# envca_4hp_2v.net
KiCad netlist of a schematic drawn in EAGLE
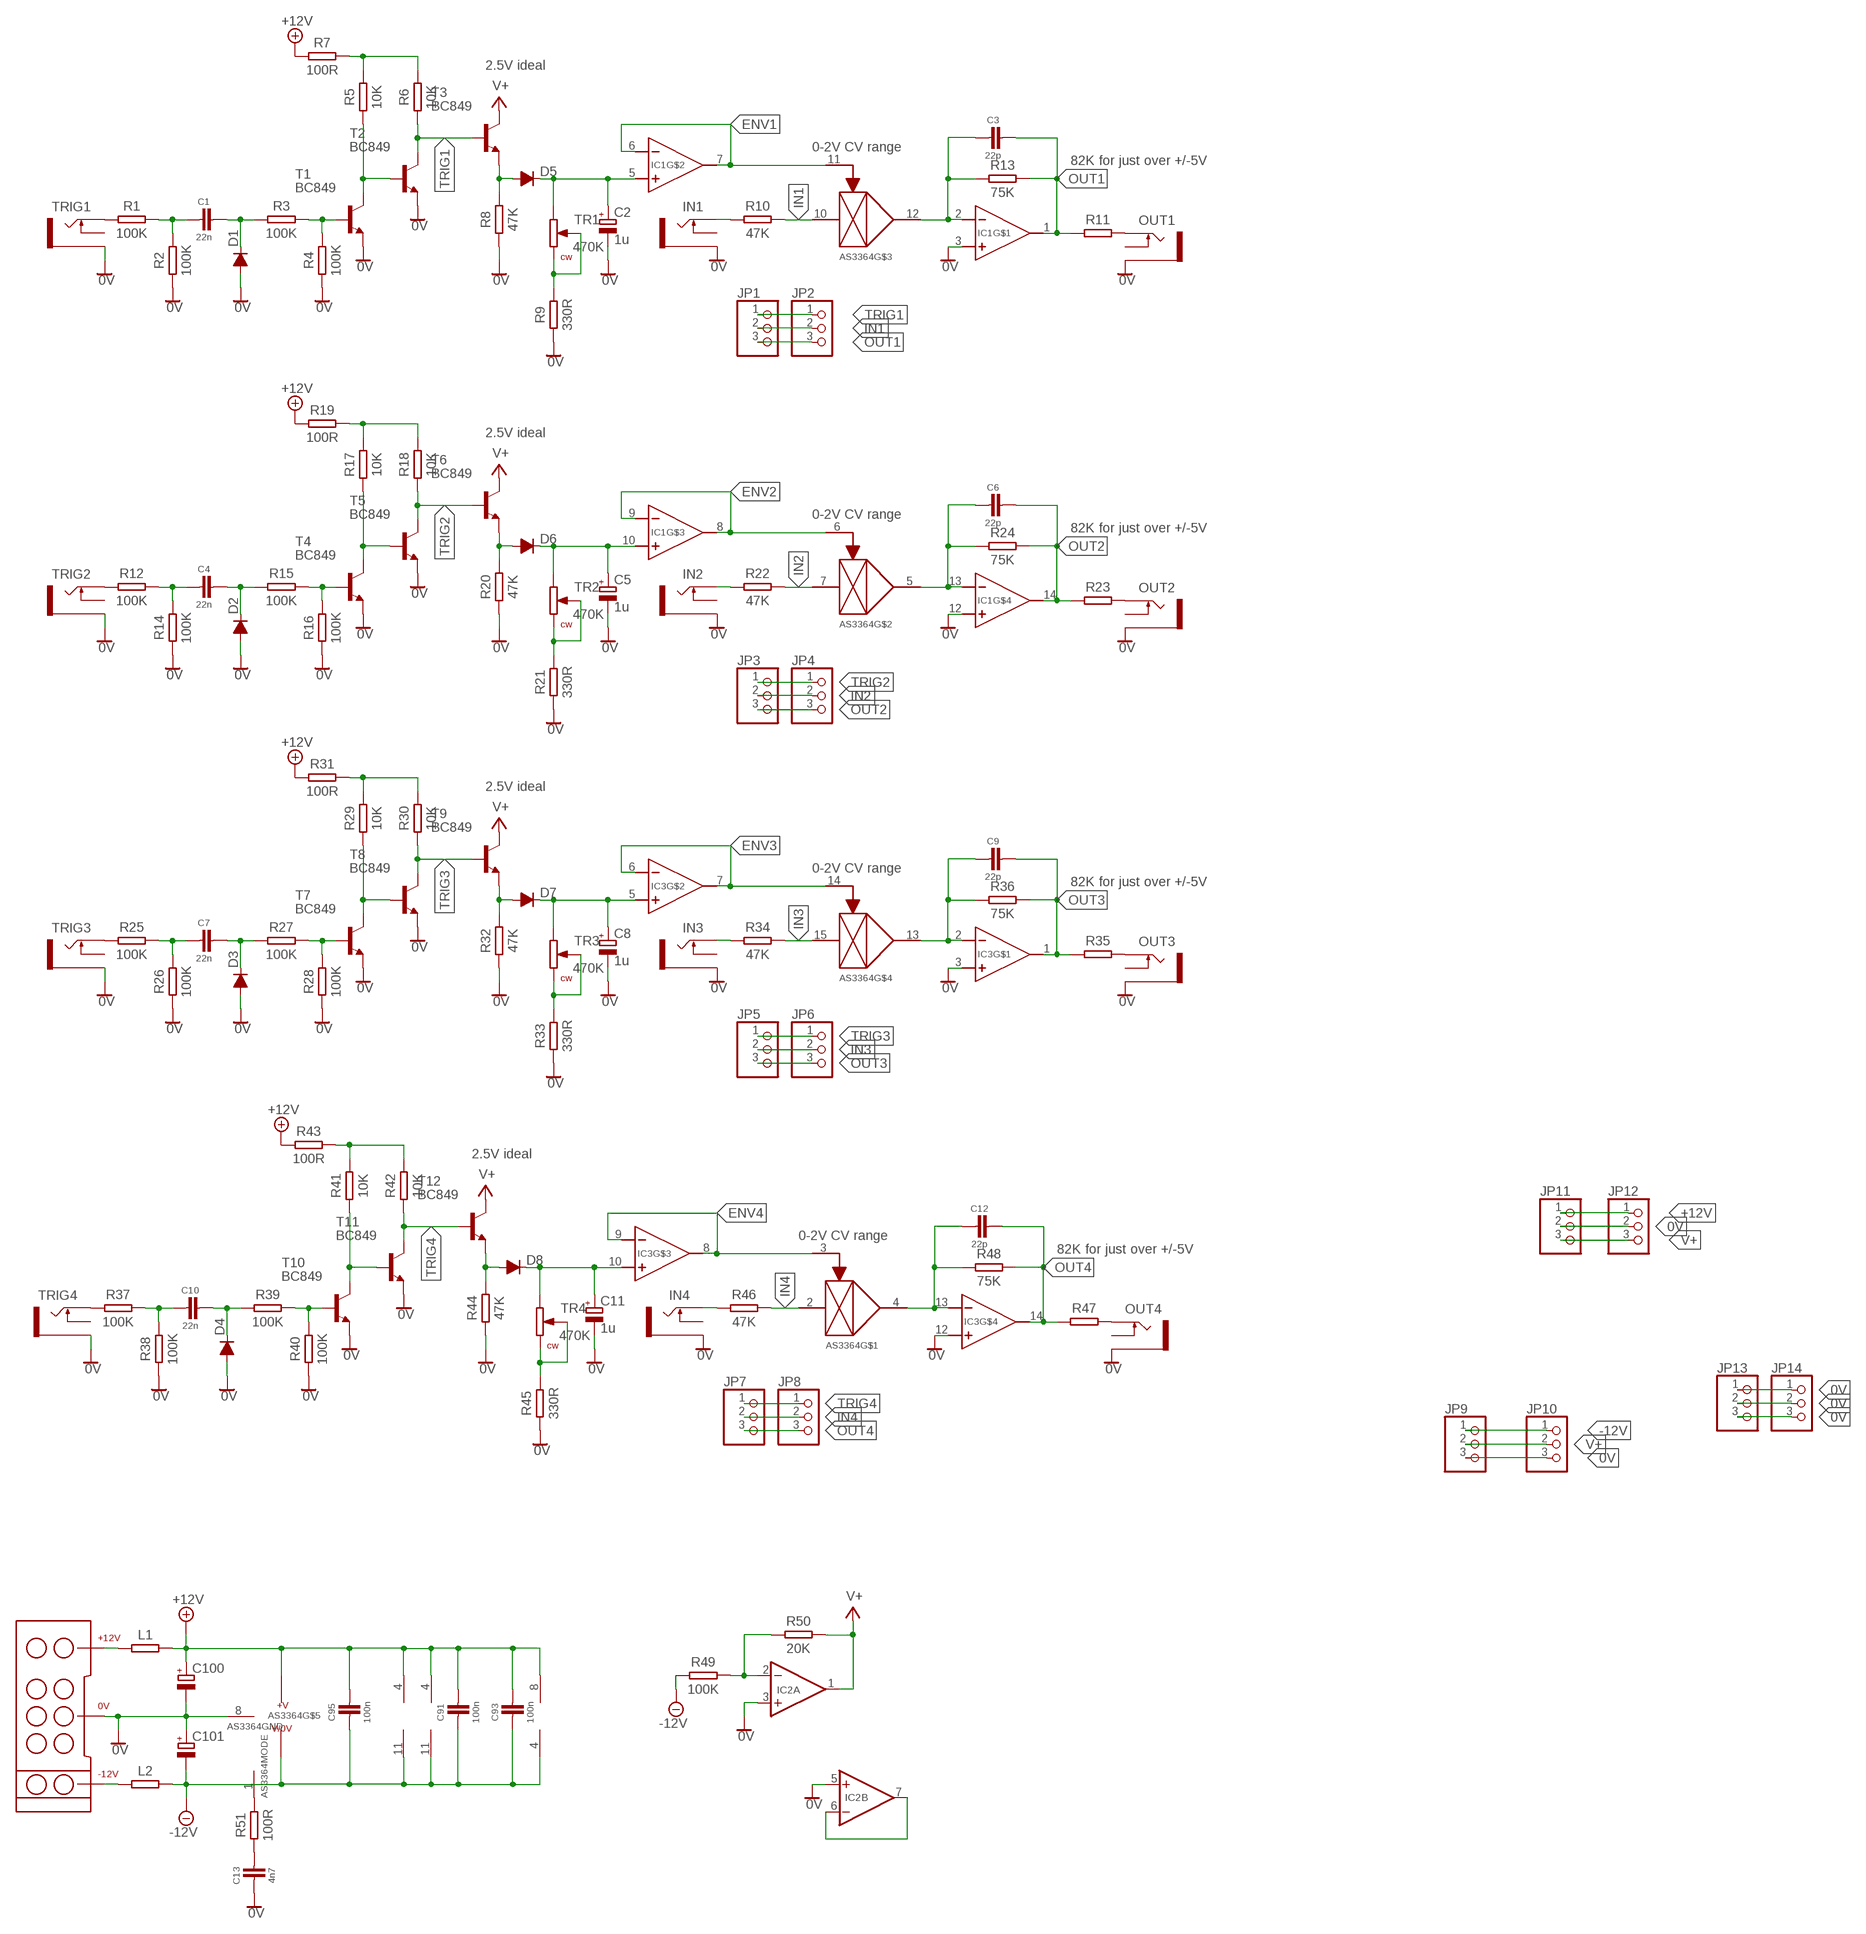
[diagram p0: schematic, sheet 1]

(export (version "E")
  (design (tool "Eeschema 10.0.6"))
  (components
    (comp (ref "AS3364")
      (value "AS2164_SMD")
      (footprint "eagle-import:SO16")
      (libsource (lib "eagle-import") (part "AS2164_SMD"))
    )
    (comp (ref "C1")
      (value "22n")
      (footprint "eagle-import:C0805")
      (libsource (lib "eagle-import") (part "CAP_0805"))
    )
    (comp (ref "C2")
      (value "1u")
      (footprint "eagle-import:E2,5-6")
      (libsource (lib "eagle-import") (part "CPOL-EUE2.5-6"))
    )
    (comp (ref "C3")
      (value "22p")
      (footprint "eagle-import:C0805")
      (libsource (lib "eagle-import") (part "CAP_0805"))
    )
    (comp (ref "C4")
      (value "22n")
      (footprint "eagle-import:C0805")
      (libsource (lib "eagle-import") (part "CAP_0805"))
    )
    (comp (ref "C5")
      (value "1u")
      (footprint "eagle-import:E2,5-6")
      (libsource (lib "eagle-import") (part "CPOL-EUE2.5-6"))
    )
    (comp (ref "C6")
      (value "22p")
      (footprint "eagle-import:C0805")
      (libsource (lib "eagle-import") (part "CAP_0805"))
    )
    (comp (ref "C7")
      (value "22n")
      (footprint "eagle-import:C0805")
      (libsource (lib "eagle-import") (part "CAP_0805"))
    )
    (comp (ref "C8")
      (value "1u")
      (footprint "eagle-import:E2,5-6")
      (libsource (lib "eagle-import") (part "CPOL-EUE2.5-6"))
    )
    (comp (ref "C9")
      (value "22p")
      (footprint "eagle-import:C0805")
      (libsource (lib "eagle-import") (part "CAP_0805"))
    )
    (comp (ref "C10")
      (value "22n")
      (footprint "eagle-import:C0805")
      (libsource (lib "eagle-import") (part "CAP_0805"))
    )
    (comp (ref "C11")
      (value "1u")
      (footprint "eagle-import:E2,5-6")
      (libsource (lib "eagle-import") (part "CPOL-EUE2.5-6"))
    )
    (comp (ref "C12")
      (value "22p")
      (footprint "eagle-import:C0805")
      (libsource (lib "eagle-import") (part "CAP_0805"))
    )
    (comp (ref "C13")
      (value "4n7")
      (footprint "eagle-import:C0805")
      (libsource (lib "eagle-import") (part "CAP_0805"))
    )
    (comp (ref "C91")
      (value "100n")
      (footprint "eagle-import:C0805")
      (libsource (lib "eagle-import") (part "CAP_0805"))
    )
    (comp (ref "C93")
      (value "100n")
      (footprint "eagle-import:C0805")
      (libsource (lib "eagle-import") (part "CAP_0805"))
    )
    (comp (ref "C95")
      (value "100n")
      (footprint "eagle-import:C0805")
      (libsource (lib "eagle-import") (part "CAP_0805"))
    )
    (comp (ref "C100")
      (value "CPOL-EUE2.5-6")
      (footprint "eagle-import:E2,5-6")
      (libsource (lib "eagle-import") (part "CPOL-EUE2.5-6"))
    )
    (comp (ref "C101")
      (value "CPOL-EUE2.5-6")
      (footprint "eagle-import:E2,5-6")
      (libsource (lib "eagle-import") (part "CPOL-EUE2.5-6"))
    )
    (comp (ref "D1")
      (value "DIODE-SOD123")
      (footprint "eagle-import:SOD123")
      (libsource (lib "eagle-import") (part "DIODE-SOD123"))
    )
    (comp (ref "D2")
      (value "DIODE-SOD123")
      (footprint "eagle-import:SOD123")
      (libsource (lib "eagle-import") (part "DIODE-SOD123"))
    )
    (comp (ref "D3")
      (value "DIODE-SOD123")
      (footprint "eagle-import:SOD123")
      (libsource (lib "eagle-import") (part "DIODE-SOD123"))
    )
    (comp (ref "D4")
      (value "DIODE-SOD123")
      (footprint "eagle-import:SOD123")
      (libsource (lib "eagle-import") (part "DIODE-SOD123"))
    )
    (comp (ref "D5")
      (value "DIODE-SOD123")
      (footprint "eagle-import:SOD123")
      (libsource (lib "eagle-import") (part "DIODE-SOD123"))
    )
    (comp (ref "D6")
      (value "DIODE-SOD123")
      (footprint "eagle-import:SOD123")
      (libsource (lib "eagle-import") (part "DIODE-SOD123"))
    )
    (comp (ref "D7")
      (value "DIODE-SOD123")
      (footprint "eagle-import:SOD123")
      (libsource (lib "eagle-import") (part "DIODE-SOD123"))
    )
    (comp (ref "D8")
      (value "DIODE-SOD123")
      (footprint "eagle-import:SOD123")
      (libsource (lib "eagle-import") (part "DIODE-SOD123"))
    )
    (comp (ref "IC1")
      (value "TL074_SO14")
      (footprint "eagle-import:SO14")
      (libsource (lib "eagle-import") (part "TL074_SO14"))
    )
    (comp (ref "IC2")
      (value "TL072_SMDD")
      (footprint "eagle-import:SO08")
      (libsource (lib "eagle-import") (part "TL072_SMDD"))
    )
    (comp (ref "IC3")
      (value "TL074_SO14")
      (footprint "eagle-import:SO14")
      (libsource (lib "eagle-import") (part "TL074_SO14"))
    )
    (comp (ref "IN1")
      (value "THONKICONN")
      (footprint "eagle-import:THONKICONN")
      (libsource (lib "eagle-import") (part "THONKICONN"))
    )
    (comp (ref "IN2")
      (value "THONKICONN")
      (footprint "eagle-import:THONKICONN")
      (libsource (lib "eagle-import") (part "THONKICONN"))
    )
    (comp (ref "IN3")
      (value "THONKICONN")
      (footprint "eagle-import:THONKICONN")
      (libsource (lib "eagle-import") (part "THONKICONN"))
    )
    (comp (ref "IN4")
      (value "THONKICONN")
      (footprint "eagle-import:THONKICONN")
      (libsource (lib "eagle-import") (part "THONKICONN"))
    )
    (comp (ref "JP1")
      (value "PINHD-1X3")
      (footprint "eagle-import:1X03")
      (libsource (lib "eagle-import") (part "PINHD-1X3"))
    )
    (comp (ref "JP2")
      (value "PINHD-1X3")
      (footprint "eagle-import:1X03")
      (libsource (lib "eagle-import") (part "PINHD-1X3"))
    )
    (comp (ref "JP3")
      (value "PINHD-1X3")
      (footprint "eagle-import:1X03")
      (libsource (lib "eagle-import") (part "PINHD-1X3"))
    )
    (comp (ref "JP4")
      (value "PINHD-1X3")
      (footprint "eagle-import:1X03")
      (libsource (lib "eagle-import") (part "PINHD-1X3"))
    )
    (comp (ref "JP5")
      (value "PINHD-1X3")
      (footprint "eagle-import:1X03")
      (libsource (lib "eagle-import") (part "PINHD-1X3"))
    )
    (comp (ref "JP6")
      (value "PINHD-1X3")
      (footprint "eagle-import:1X03")
      (libsource (lib "eagle-import") (part "PINHD-1X3"))
    )
    (comp (ref "JP7")
      (value "PINHD-1X3")
      (footprint "eagle-import:1X03")
      (libsource (lib "eagle-import") (part "PINHD-1X3"))
    )
    (comp (ref "JP8")
      (value "PINHD-1X3")
      (footprint "eagle-import:1X03")
      (libsource (lib "eagle-import") (part "PINHD-1X3"))
    )
    (comp (ref "JP9")
      (value "PINHD-1X3")
      (footprint "eagle-import:1X03")
      (libsource (lib "eagle-import") (part "PINHD-1X3"))
    )
    (comp (ref "JP10")
      (value "PINHD-1X3")
      (footprint "eagle-import:1X03")
      (libsource (lib "eagle-import") (part "PINHD-1X3"))
    )
    (comp (ref "JP11")
      (value "PINHD-1X3")
      (footprint "eagle-import:1X03")
      (libsource (lib "eagle-import") (part "PINHD-1X3"))
    )
    (comp (ref "JP12")
      (value "PINHD-1X3")
      (footprint "eagle-import:1X03")
      (libsource (lib "eagle-import") (part "PINHD-1X3"))
    )
    (comp (ref "JP13")
      (value "PINHD-1X3")
      (footprint "eagle-import:1X03")
      (libsource (lib "eagle-import") (part "PINHD-1X3"))
    )
    (comp (ref "JP14")
      (value "PINHD-1X3")
      (footprint "eagle-import:1X03")
      (libsource (lib "eagle-import") (part "PINHD-1X3"))
    )
    (comp (ref "L1")
      (value "RESISTOR_0805")
      (footprint "eagle-import:R0805")
      (libsource (lib "eagle-import") (part "RESISTOR_0805"))
    )
    (comp (ref "L2")
      (value "RESISTOR_0805")
      (footprint "eagle-import:R0805")
      (libsource (lib "eagle-import") (part "RESISTOR_0805"))
    )
    (comp (ref "OUT1")
      (value "THONKICONN")
      (footprint "eagle-import:THONKICONN")
      (libsource (lib "eagle-import") (part "THONKICONN"))
    )
    (comp (ref "OUT2")
      (value "THONKICONN")
      (footprint "eagle-import:THONKICONN")
      (libsource (lib "eagle-import") (part "THONKICONN"))
    )
    (comp (ref "OUT3")
      (value "THONKICONN")
      (footprint "eagle-import:THONKICONN")
      (libsource (lib "eagle-import") (part "THONKICONN"))
    )
    (comp (ref "OUT4")
      (value "THONKICONN")
      (footprint "eagle-import:THONKICONN")
      (libsource (lib "eagle-import") (part "THONKICONN"))
    )
    (comp (ref "R1")
      (value "100K")
      (footprint "eagle-import:R0805")
      (libsource (lib "eagle-import") (part "RESISTOR_0805"))
    )
    (comp (ref "R2")
      (value "100K")
      (footprint "eagle-import:R0805")
      (libsource (lib "eagle-import") (part "RESISTOR_0805"))
    )
    (comp (ref "R3")
      (value "100K")
      (footprint "eagle-import:R0805")
      (libsource (lib "eagle-import") (part "RESISTOR_0805"))
    )
    (comp (ref "R4")
      (value "100K")
      (footprint "eagle-import:R0805")
      (libsource (lib "eagle-import") (part "RESISTOR_0805"))
    )
    (comp (ref "R5")
      (value "10K")
      (footprint "eagle-import:R0805")
      (libsource (lib "eagle-import") (part "RESISTOR_0805"))
    )
    (comp (ref "R6")
      (value "10K")
      (footprint "eagle-import:R0805")
      (libsource (lib "eagle-import") (part "RESISTOR_0805"))
    )
    (comp (ref "R7")
      (value "100R")
      (footprint "eagle-import:R0805")
      (libsource (lib "eagle-import") (part "RESISTOR_0805"))
    )
    (comp (ref "R8")
      (value "47K")
      (footprint "eagle-import:R0805")
      (libsource (lib "eagle-import") (part "RESISTOR_0805"))
    )
    (comp (ref "R9")
      (value "330R")
      (footprint "eagle-import:R0805")
      (libsource (lib "eagle-import") (part "RESISTOR_0805"))
    )
    (comp (ref "R10")
      (value "47K")
      (footprint "eagle-import:R0805")
      (libsource (lib "eagle-import") (part "RESISTOR_0805"))
    )
    (comp (ref "R11")
      (value "RESISTOR_0805")
      (footprint "eagle-import:R0805")
      (libsource (lib "eagle-import") (part "RESISTOR_0805"))
    )
    (comp (ref "R12")
      (value "100K")
      (footprint "eagle-import:R0805")
      (libsource (lib "eagle-import") (part "RESISTOR_0805"))
    )
    (comp (ref "R13")
      (value "75K")
      (footprint "eagle-import:R0805")
      (libsource (lib "eagle-import") (part "RESISTOR_0805"))
    )
    (comp (ref "R14")
      (value "100K")
      (footprint "eagle-import:R0805")
      (libsource (lib "eagle-import") (part "RESISTOR_0805"))
    )
    (comp (ref "R15")
      (value "100K")
      (footprint "eagle-import:R0805")
      (libsource (lib "eagle-import") (part "RESISTOR_0805"))
    )
    (comp (ref "R16")
      (value "100K")
      (footprint "eagle-import:R0805")
      (libsource (lib "eagle-import") (part "RESISTOR_0805"))
    )
    (comp (ref "R17")
      (value "10K")
      (footprint "eagle-import:R0805")
      (libsource (lib "eagle-import") (part "RESISTOR_0805"))
    )
    (comp (ref "R18")
      (value "10K")
      (footprint "eagle-import:R0805")
      (libsource (lib "eagle-import") (part "RESISTOR_0805"))
    )
    (comp (ref "R19")
      (value "100R")
      (footprint "eagle-import:R0805")
      (libsource (lib "eagle-import") (part "RESISTOR_0805"))
    )
    (comp (ref "R20")
      (value "47K")
      (footprint "eagle-import:R0805")
      (libsource (lib "eagle-import") (part "RESISTOR_0805"))
    )
    (comp (ref "R21")
      (value "330R")
      (footprint "eagle-import:R0805")
      (libsource (lib "eagle-import") (part "RESISTOR_0805"))
    )
    (comp (ref "R22")
      (value "47K")
      (footprint "eagle-import:R0805")
      (libsource (lib "eagle-import") (part "RESISTOR_0805"))
    )
    (comp (ref "R23")
      (value "RESISTOR_0805")
      (footprint "eagle-import:R0805")
      (libsource (lib "eagle-import") (part "RESISTOR_0805"))
    )
    (comp (ref "R24")
      (value "75K")
      (footprint "eagle-import:R0805")
      (libsource (lib "eagle-import") (part "RESISTOR_0805"))
    )
    (comp (ref "R25")
      (value "100K")
      (footprint "eagle-import:R0805")
      (libsource (lib "eagle-import") (part "RESISTOR_0805"))
    )
    (comp (ref "R26")
      (value "100K")
      (footprint "eagle-import:R0805")
      (libsource (lib "eagle-import") (part "RESISTOR_0805"))
    )
    (comp (ref "R27")
      (value "100K")
      (footprint "eagle-import:R0805")
      (libsource (lib "eagle-import") (part "RESISTOR_0805"))
    )
    (comp (ref "R28")
      (value "100K")
      (footprint "eagle-import:R0805")
      (libsource (lib "eagle-import") (part "RESISTOR_0805"))
    )
    (comp (ref "R29")
      (value "10K")
      (footprint "eagle-import:R0805")
      (libsource (lib "eagle-import") (part "RESISTOR_0805"))
    )
    (comp (ref "R30")
      (value "10K")
      (footprint "eagle-import:R0805")
      (libsource (lib "eagle-import") (part "RESISTOR_0805"))
    )
    (comp (ref "R31")
      (value "100R")
      (footprint "eagle-import:R0805")
      (libsource (lib "eagle-import") (part "RESISTOR_0805"))
    )
    (comp (ref "R32")
      (value "47K")
      (footprint "eagle-import:R0805")
      (libsource (lib "eagle-import") (part "RESISTOR_0805"))
    )
    (comp (ref "R33")
      (value "330R")
      (footprint "eagle-import:R0805")
      (libsource (lib "eagle-import") (part "RESISTOR_0805"))
    )
    (comp (ref "R34")
      (value "47K")
      (footprint "eagle-import:R0805")
      (libsource (lib "eagle-import") (part "RESISTOR_0805"))
    )
    (comp (ref "R35")
      (value "RESISTOR_0805")
      (footprint "eagle-import:R0805")
      (libsource (lib "eagle-import") (part "RESISTOR_0805"))
    )
    (comp (ref "R36")
      (value "75K")
      (footprint "eagle-import:R0805")
      (libsource (lib "eagle-import") (part "RESISTOR_0805"))
    )
    (comp (ref "R37")
      (value "100K")
      (footprint "eagle-import:R0805")
      (libsource (lib "eagle-import") (part "RESISTOR_0805"))
    )
    (comp (ref "R38")
      (value "100K")
      (footprint "eagle-import:R0805")
      (libsource (lib "eagle-import") (part "RESISTOR_0805"))
    )
    (comp (ref "R39")
      (value "100K")
      (footprint "eagle-import:R0805")
      (libsource (lib "eagle-import") (part "RESISTOR_0805"))
    )
    (comp (ref "R40")
      (value "100K")
      (footprint "eagle-import:R0805")
      (libsource (lib "eagle-import") (part "RESISTOR_0805"))
    )
    (comp (ref "R41")
      (value "10K")
      (footprint "eagle-import:R0805")
      (libsource (lib "eagle-import") (part "RESISTOR_0805"))
    )
    (comp (ref "R42")
      (value "10K")
      (footprint "eagle-import:R0805")
      (libsource (lib "eagle-import") (part "RESISTOR_0805"))
    )
    (comp (ref "R43")
      (value "100R")
      (footprint "eagle-import:R0805")
      (libsource (lib "eagle-import") (part "RESISTOR_0805"))
    )
    (comp (ref "R44")
      (value "47K")
      (footprint "eagle-import:R0805")
      (libsource (lib "eagle-import") (part "RESISTOR_0805"))
    )
    (comp (ref "R45")
      (value "330R")
      (footprint "eagle-import:R0805")
      (libsource (lib "eagle-import") (part "RESISTOR_0805"))
    )
    (comp (ref "R46")
      (value "47K")
      (footprint "eagle-import:R0805")
      (libsource (lib "eagle-import") (part "RESISTOR_0805"))
    )
    (comp (ref "R47")
      (value "RESISTOR_0805")
      (footprint "eagle-import:R0805")
      (libsource (lib "eagle-import") (part "RESISTOR_0805"))
    )
    (comp (ref "R48")
      (value "75K")
      (footprint "eagle-import:R0805")
      (libsource (lib "eagle-import") (part "RESISTOR_0805"))
    )
    (comp (ref "R49")
      (value "100K")
      (footprint "eagle-import:R0805")
      (libsource (lib "eagle-import") (part "RESISTOR_0805"))
    )
    (comp (ref "R50")
      (value "20K")
      (footprint "eagle-import:R0805")
      (libsource (lib "eagle-import") (part "RESISTOR_0805"))
    )
    (comp (ref "R51")
      (value "100R")
      (footprint "eagle-import:R0805")
      (libsource (lib "eagle-import") (part "RESISTOR_0805"))
    )
    (comp (ref "T1")
      (value "BC849")
      (footprint "eagle-import:SOT23")
      (libsource (lib "eagle-import") (part "BC849"))
    )
    (comp (ref "T2")
      (value "BC849")
      (footprint "eagle-import:SOT23")
      (libsource (lib "eagle-import") (part "BC849"))
    )
    (comp (ref "T3")
      (value "BC849")
      (footprint "eagle-import:SOT23")
      (libsource (lib "eagle-import") (part "BC849"))
    )
    (comp (ref "T4")
      (value "BC849")
      (footprint "eagle-import:SOT23")
      (libsource (lib "eagle-import") (part "BC849"))
    )
    (comp (ref "T5")
      (value "BC849")
      (footprint "eagle-import:SOT23")
      (libsource (lib "eagle-import") (part "BC849"))
    )
    (comp (ref "T6")
      (value "BC849")
      (footprint "eagle-import:SOT23")
      (libsource (lib "eagle-import") (part "BC849"))
    )
    (comp (ref "T7")
      (value "BC849")
      (footprint "eagle-import:SOT23")
      (libsource (lib "eagle-import") (part "BC849"))
    )
    (comp (ref "T8")
      (value "BC849")
      (footprint "eagle-import:SOT23")
      (libsource (lib "eagle-import") (part "BC849"))
    )
    (comp (ref "T9")
      (value "BC849")
      (footprint "eagle-import:SOT23")
      (libsource (lib "eagle-import") (part "BC849"))
    )
    (comp (ref "T10")
      (value "BC849")
      (footprint "eagle-import:SOT23")
      (libsource (lib "eagle-import") (part "BC849"))
    )
    (comp (ref "T11")
      (value "BC849")
      (footprint "eagle-import:SOT23")
      (libsource (lib "eagle-import") (part "BC849"))
    )
    (comp (ref "T12")
      (value "BC849")
      (footprint "eagle-import:SOT23")
      (libsource (lib "eagle-import") (part "BC849"))
    )
    (comp (ref "TR1")
      (value "470K")
      (footprint "eagle-import:TRIMMER3362")
      (libsource (lib "eagle-import") (part "TRIMMER-3362"))
    )
    (comp (ref "TR2")
      (value "470K")
      (footprint "eagle-import:TRIMMER3362")
      (libsource (lib "eagle-import") (part "TRIMMER-3362"))
    )
    (comp (ref "TR3")
      (value "470K")
      (footprint "eagle-import:TRIMMER3362")
      (libsource (lib "eagle-import") (part "TRIMMER-3362"))
    )
    (comp (ref "TR4")
      (value "470K")
      (footprint "eagle-import:TRIMMER3362")
      (libsource (lib "eagle-import") (part "TRIMMER-3362"))
    )
    (comp (ref "TRIG1")
      (value "THONKICONN")
      (footprint "eagle-import:THONKICONN")
      (libsource (lib "eagle-import") (part "THONKICONN"))
    )
    (comp (ref "TRIG2")
      (value "THONKICONN")
      (footprint "eagle-import:THONKICONN")
      (libsource (lib "eagle-import") (part "THONKICONN"))
    )
    (comp (ref "TRIG3")
      (value "THONKICONN")
      (footprint "eagle-import:THONKICONN")
      (libsource (lib "eagle-import") (part "THONKICONN"))
    )
    (comp (ref "TRIG4")
      (value "THONKICONN")
      (footprint "eagle-import:THONKICONN")
      (libsource (lib "eagle-import") (part "THONKICONN"))
    )
    (comp (ref "U$1")
      (value "EURO_POWER")
      (footprint "eagle-import:EURO_POWER")
      (libsource (lib "eagle-import") (part "EURO_POWER"))
    )
  )
  (nets
    (net (code "1") (name "+12V") (class "Default")
      (node (ref "AS3364") (pin "16") (pinfunction "VDD_16") (pintype "power_in"))
      (node (ref "C100") (pin "+") (pinfunction "+_+") (pintype "passive"))
      (node (ref "C91") (pin "2") (pinfunction "2_2") (pintype "passive"))
      (node (ref "C93") (pin "2") (pinfunction "2_2") (pintype "passive"))
      (node (ref "C95") (pin "2") (pinfunction "2_2") (pintype "passive"))
      (node (ref "IC1") (pin "4") (pinfunction "V+_4") (pintype "power_in"))
      (node (ref "IC2") (pin "8") (pinfunction "V+_8") (pintype "power_in"))
      (node (ref "IC3") (pin "4") (pinfunction "V+_4") (pintype "power_in"))
      (node (ref "JP11") (pin "1") (pinfunction "1_1") (pintype "passive"))
      (node (ref "JP12") (pin "1") (pinfunction "1_1") (pintype "passive"))
      (node (ref "L1") (pin "2") (pinfunction "2_2") (pintype "passive"))
      (node (ref "R19") (pin "1") (pinfunction "1_1") (pintype "passive"))
      (node (ref "R31") (pin "1") (pinfunction "1_1") (pintype "passive"))
      (node (ref "R43") (pin "1") (pinfunction "1_1") (pintype "passive"))
      (node (ref "R7") (pin "1") (pinfunction "1_1") (pintype "passive"))
    )
    (net (code "2") (name "-12V") (class "Default")
      (node (ref "AS3364") (pin "9") (pinfunction "VSS_9") (pintype "power_in"))
      (node (ref "C101") (pin "-") (pinfunction "-_-") (pintype "passive"))
      (node (ref "C91") (pin "1") (pinfunction "1_1") (pintype "passive"))
      (node (ref "C93") (pin "1") (pinfunction "1_1") (pintype "passive"))
      (node (ref "C95") (pin "1") (pinfunction "1_1") (pintype "passive"))
      (node (ref "IC1") (pin "11") (pinfunction "V-_11") (pintype "power_in"))
      (node (ref "IC2") (pin "4") (pinfunction "V-_4") (pintype "power_in"))
      (node (ref "IC3") (pin "11") (pinfunction "V-_11") (pintype "power_in"))
      (node (ref "JP10") (pin "1") (pinfunction "1_1") (pintype "passive"))
      (node (ref "JP9") (pin "1") (pinfunction "1_1") (pintype "passive"))
      (node (ref "L2") (pin "2") (pinfunction "2_2") (pintype "passive"))
      (node (ref "R49") (pin "1") (pinfunction "1_1") (pintype "passive"))
    )
    (net (code "3") (name "0V") (class "Default")
      (node (ref "AS3364") (pin "8") (pinfunction "P$1_8") (pintype "bidirectional"))
      (node (ref "C100") (pin "-") (pinfunction "-_-") (pintype "passive"))
      (node (ref "C101") (pin "+") (pinfunction "+_+") (pintype "passive"))
      (node (ref "C11") (pin "-") (pinfunction "-_-") (pintype "passive"))
      (node (ref "C13") (pin "1") (pinfunction "1_1") (pintype "passive"))
      (node (ref "C2") (pin "-") (pinfunction "-_-") (pintype "passive"))
      (node (ref "C5") (pin "-") (pinfunction "-_-") (pintype "passive"))
      (node (ref "C8") (pin "-") (pinfunction "-_-") (pintype "passive"))
      (node (ref "D1") (pin "A") (pinfunction "A_A") (pintype "passive"))
      (node (ref "D2") (pin "A") (pinfunction "A_A") (pintype "passive"))
      (node (ref "D3") (pin "A") (pinfunction "A_A") (pintype "passive"))
      (node (ref "D4") (pin "A") (pinfunction "A_A") (pintype "passive"))
      (node (ref "IC1") (pin "12") (pinfunction "+_12") (pintype "input"))
      (node (ref "IC1") (pin "3") (pinfunction "+_3") (pintype "input"))
      (node (ref "IC2") (pin "3") (pinfunction "+IN_3") (pintype "input"))
      (node (ref "IC2") (pin "5") (pinfunction "+IN_5") (pintype "input"))
      (node (ref "IC3") (pin "12") (pinfunction "+_12") (pintype "input"))
      (node (ref "IC3") (pin "3") (pinfunction "+_3") (pintype "input"))
      (node (ref "IN1") (pin "P$3_SLEEVE") (pinfunction "SLEEVE_P$3_SLEEVE") (pintype "passive"))
      (node (ref "IN2") (pin "P$3_SLEEVE") (pinfunction "SLEEVE_P$3_SLEEVE") (pintype "passive"))
      (node (ref "IN3") (pin "P$3_SLEEVE") (pinfunction "SLEEVE_P$3_SLEEVE") (pintype "passive"))
      (node (ref "IN4") (pin "P$3_SLEEVE") (pinfunction "SLEEVE_P$3_SLEEVE") (pintype "passive"))
      (node (ref "JP10") (pin "3") (pinfunction "3_3") (pintype "passive"))
      (node (ref "JP11") (pin "2") (pinfunction "2_2") (pintype "passive"))
      (node (ref "JP12") (pin "2") (pinfunction "2_2") (pintype "passive"))
      (node (ref "JP13") (pin "1") (pinfunction "1_1") (pintype "passive"))
      (node (ref "JP13") (pin "2") (pinfunction "2_2") (pintype "passive"))
      (node (ref "JP13") (pin "3") (pinfunction "3_3") (pintype "passive"))
      (node (ref "JP14") (pin "1") (pinfunction "1_1") (pintype "passive"))
      (node (ref "JP14") (pin "2") (pinfunction "2_2") (pintype "passive"))
      (node (ref "JP14") (pin "3") (pinfunction "3_3") (pintype "passive"))
      (node (ref "JP9") (pin "3") (pinfunction "3_3") (pintype "passive"))
      (node (ref "OUT1") (pin "P$3_SLEEVE") (pinfunction "SLEEVE_P$3_SLEEVE") (pintype "passive"))
      (node (ref "OUT2") (pin "P$3_SLEEVE") (pinfunction "SLEEVE_P$3_SLEEVE") (pintype "passive"))
      (node (ref "OUT3") (pin "P$3_SLEEVE") (pinfunction "SLEEVE_P$3_SLEEVE") (pintype "passive"))
      (node (ref "OUT4") (pin "P$3_SLEEVE") (pinfunction "SLEEVE_P$3_SLEEVE") (pintype "passive"))
      (node (ref "R14") (pin "1") (pinfunction "1_1") (pintype "passive"))
      (node (ref "R16") (pin "1") (pinfunction "1_1") (pintype "passive"))
      (node (ref "R2") (pin "1") (pinfunction "1_1") (pintype "passive"))
      (node (ref "R20") (pin "1") (pinfunction "1_1") (pintype "passive"))
      (node (ref "R21") (pin "1") (pinfunction "1_1") (pintype "passive"))
      (node (ref "R26") (pin "1") (pinfunction "1_1") (pintype "passive"))
      (node (ref "R28") (pin "1") (pinfunction "1_1") (pintype "passive"))
      (node (ref "R32") (pin "1") (pinfunction "1_1") (pintype "passive"))
      (node (ref "R33") (pin "1") (pinfunction "1_1") (pintype "passive"))
      (node (ref "R38") (pin "1") (pinfunction "1_1") (pintype "passive"))
      (node (ref "R4") (pin "1") (pinfunction "1_1") (pintype "passive"))
      (node (ref "R40") (pin "1") (pinfunction "1_1") (pintype "passive"))
      (node (ref "R44") (pin "1") (pinfunction "1_1") (pintype "passive"))
      (node (ref "R45") (pin "1") (pinfunction "1_1") (pintype "passive"))
      (node (ref "R8") (pin "1") (pinfunction "1_1") (pintype "passive"))
      (node (ref "R9") (pin "1") (pinfunction "1_1") (pintype "passive"))
      (node (ref "T1") (pin "2") (pinfunction "E_2") (pintype "passive"))
      (node (ref "T10") (pin "2") (pinfunction "E_2") (pintype "passive"))
      (node (ref "T11") (pin "2") (pinfunction "E_2") (pintype "passive"))
      (node (ref "T2") (pin "2") (pinfunction "E_2") (pintype "passive"))
      (node (ref "T4") (pin "2") (pinfunction "E_2") (pintype "passive"))
      (node (ref "T5") (pin "2") (pinfunction "E_2") (pintype "passive"))
      (node (ref "T7") (pin "2") (pinfunction "E_2") (pintype "passive"))
      (node (ref "T8") (pin "2") (pinfunction "E_2") (pintype "passive"))
      (node (ref "TRIG1") (pin "P$3_SLEEVE") (pinfunction "SLEEVE_P$3_SLEEVE") (pintype "passive"))
      (node (ref "TRIG2") (pin "P$3_SLEEVE") (pinfunction "SLEEVE_P$3_SLEEVE") (pintype "passive"))
      (node (ref "TRIG3") (pin "P$3_SLEEVE") (pinfunction "SLEEVE_P$3_SLEEVE") (pintype "passive"))
      (node (ref "TRIG4") (pin "P$3_SLEEVE") (pinfunction "SLEEVE_P$3_SLEEVE") (pintype "passive"))
      (node (ref "U$1") (pin "3") (pinfunction "0V_3") (pintype "bidirectional"))
      (node (ref "U$1") (pin "4") (pinfunction "0V_4") (pintype "bidirectional"))
      (node (ref "U$1") (pin "5") (pinfunction "0V_5") (pintype "bidirectional"))
      (node (ref "U$1") (pin "6") (pinfunction "0V_6") (pintype "bidirectional"))
      (node (ref "U$1") (pin "7") (pinfunction "0V_7") (pintype "bidirectional"))
      (node (ref "U$1") (pin "8") (pinfunction "0V_8") (pintype "bidirectional"))
    )
    (net (code "4") (name "ENV1") (class "Default")
      (node (ref "AS3364") (pin "11") (pinfunction "VC_11") (pintype "bidirectional"))
      (node (ref "IC1") (pin "6") (pinfunction "-_6") (pintype "input"))
      (node (ref "IC1") (pin "7") (pinfunction "OUT_7") (pintype "output"))
    )
    (net (code "5") (name "ENV2") (class "Default")
      (node (ref "AS3364") (pin "6") (pinfunction "VC_6") (pintype "bidirectional"))
      (node (ref "IC1") (pin "8") (pinfunction "OUT_8") (pintype "output"))
      (node (ref "IC1") (pin "9") (pinfunction "-_9") (pintype "input"))
    )
    (net (code "6") (name "ENV3") (class "Default")
      (node (ref "AS3364") (pin "14") (pinfunction "VC_14") (pintype "bidirectional"))
      (node (ref "IC3") (pin "6") (pinfunction "-_6") (pintype "input"))
      (node (ref "IC3") (pin "7") (pinfunction "OUT_7") (pintype "output"))
    )
    (net (code "7") (name "ENV4") (class "Default")
      (node (ref "AS3364") (pin "3") (pinfunction "VC_3") (pintype "bidirectional"))
      (node (ref "IC3") (pin "8") (pinfunction "OUT_8") (pintype "output"))
      (node (ref "IC3") (pin "9") (pinfunction "-_9") (pintype "input"))
    )
    (net (code "8") (name "IN1") (class "Default")
      (node (ref "AS3364") (pin "10") (pinfunction "IN_10") (pintype "bidirectional"))
      (node (ref "JP1") (pin "2") (pinfunction "2_2") (pintype "passive"))
      (node (ref "JP2") (pin "2") (pinfunction "2_2") (pintype "passive"))
      (node (ref "R10") (pin "2") (pinfunction "2_2") (pintype "passive"))
    )
    (net (code "9") (name "IN2") (class "Default")
      (node (ref "AS3364") (pin "7") (pinfunction "IN_7") (pintype "bidirectional"))
      (node (ref "JP3") (pin "2") (pinfunction "2_2") (pintype "passive"))
      (node (ref "JP4") (pin "2") (pinfunction "2_2") (pintype "passive"))
      (node (ref "R22") (pin "2") (pinfunction "2_2") (pintype "passive"))
    )
    (net (code "10") (name "IN3") (class "Default")
      (node (ref "AS3364") (pin "15") (pinfunction "IN_15") (pintype "bidirectional"))
      (node (ref "JP5") (pin "2") (pinfunction "2_2") (pintype "passive"))
      (node (ref "JP6") (pin "2") (pinfunction "2_2") (pintype "passive"))
      (node (ref "R34") (pin "2") (pinfunction "2_2") (pintype "passive"))
    )
    (net (code "11") (name "IN4") (class "Default")
      (node (ref "AS3364") (pin "2") (pinfunction "IN_2") (pintype "bidirectional"))
      (node (ref "JP7") (pin "2") (pinfunction "2_2") (pintype "passive"))
      (node (ref "JP8") (pin "2") (pinfunction "2_2") (pintype "passive"))
      (node (ref "R46") (pin "2") (pinfunction "2_2") (pintype "passive"))
    )
    (net (code "12") (name "Net-(AS3364A-OUT)") (class "Default")
      (node (ref "AS3364") (pin "4") (pinfunction "OUT_4") (pintype "bidirectional"))
      (node (ref "C12") (pin "1") (pinfunction "1_1") (pintype "passive"))
      (node (ref "IC3") (pin "13") (pinfunction "-_13") (pintype "input"))
      (node (ref "R48") (pin "1") (pinfunction "1_1") (pintype "passive"))
    )
    (net (code "13") (name "Net-(AS3364B-OUT)") (class "Default")
      (node (ref "AS3364") (pin "5") (pinfunction "OUT_5") (pintype "bidirectional"))
      (node (ref "C6") (pin "1") (pinfunction "1_1") (pintype "passive"))
      (node (ref "IC1") (pin "13") (pinfunction "-_13") (pintype "input"))
      (node (ref "R24") (pin "1") (pinfunction "1_1") (pintype "passive"))
    )
    (net (code "14") (name "Net-(AS3364C-OUT)") (class "Default")
      (node (ref "AS3364") (pin "12") (pinfunction "OUT_12") (pintype "bidirectional"))
      (node (ref "C3") (pin "1") (pinfunction "1_1") (pintype "passive"))
      (node (ref "IC1") (pin "2") (pinfunction "-_2") (pintype "input"))
      (node (ref "R13") (pin "1") (pinfunction "1_1") (pintype "passive"))
    )
    (net (code "15") (name "Net-(AS3364D-OUT)") (class "Default")
      (node (ref "AS3364") (pin "13") (pinfunction "OUT_13") (pintype "bidirectional"))
      (node (ref "C9") (pin "1") (pinfunction "1_1") (pintype "passive"))
      (node (ref "IC3") (pin "2") (pinfunction "-_2") (pintype "input"))
      (node (ref "R36") (pin "1") (pinfunction "1_1") (pintype "passive"))
    )
    (net (code "16") (name "Net-(AS3364G-P$1)") (class "Default")
      (node (ref "AS3364") (pin "1") (pinfunction "P$1_1") (pintype "bidirectional"))
      (node (ref "R51") (pin "2") (pinfunction "2_2") (pintype "passive"))
    )
    (net (code "17") (name "Net-(C1-Pad1)") (class "Default")
      (node (ref "C1") (pin "1") (pinfunction "1_1") (pintype "passive"))
      (node (ref "R1") (pin "2") (pinfunction "2_2") (pintype "passive"))
      (node (ref "R2") (pin "2") (pinfunction "2_2") (pintype "passive"))
    )
    (net (code "18") (name "Net-(C1-Pad2)") (class "Default")
      (node (ref "C1") (pin "2") (pinfunction "2_2") (pintype "passive"))
      (node (ref "D1") (pin "C") (pinfunction "C_C") (pintype "passive"))
      (node (ref "R3") (pin "1") (pinfunction "1_1") (pintype "passive"))
    )
    (net (code "19") (name "Net-(C4-Pad1)") (class "Default")
      (node (ref "C4") (pin "1") (pinfunction "1_1") (pintype "passive"))
      (node (ref "R12") (pin "2") (pinfunction "2_2") (pintype "passive"))
      (node (ref "R14") (pin "2") (pinfunction "2_2") (pintype "passive"))
    )
    (net (code "20") (name "Net-(C4-Pad2)") (class "Default")
      (node (ref "C4") (pin "2") (pinfunction "2_2") (pintype "passive"))
      (node (ref "D2") (pin "C") (pinfunction "C_C") (pintype "passive"))
      (node (ref "R15") (pin "1") (pinfunction "1_1") (pintype "passive"))
    )
    (net (code "21") (name "Net-(C7-Pad1)") (class "Default")
      (node (ref "C7") (pin "1") (pinfunction "1_1") (pintype "passive"))
      (node (ref "R25") (pin "2") (pinfunction "2_2") (pintype "passive"))
      (node (ref "R26") (pin "2") (pinfunction "2_2") (pintype "passive"))
    )
    (net (code "22") (name "Net-(C7-Pad2)") (class "Default")
      (node (ref "C7") (pin "2") (pinfunction "2_2") (pintype "passive"))
      (node (ref "D3") (pin "C") (pinfunction "C_C") (pintype "passive"))
      (node (ref "R27") (pin "1") (pinfunction "1_1") (pintype "passive"))
    )
    (net (code "23") (name "Net-(C10-Pad1)") (class "Default")
      (node (ref "C10") (pin "1") (pinfunction "1_1") (pintype "passive"))
      (node (ref "R37") (pin "2") (pinfunction "2_2") (pintype "passive"))
      (node (ref "R38") (pin "2") (pinfunction "2_2") (pintype "passive"))
    )
    (net (code "24") (name "Net-(C10-Pad2)") (class "Default")
      (node (ref "C10") (pin "2") (pinfunction "2_2") (pintype "passive"))
      (node (ref "D4") (pin "C") (pinfunction "C_C") (pintype "passive"))
      (node (ref "R39") (pin "1") (pinfunction "1_1") (pintype "passive"))
    )
    (net (code "25") (name "Net-(C13-Pad2)") (class "Default")
      (node (ref "C13") (pin "2") (pinfunction "2_2") (pintype "passive"))
      (node (ref "R51") (pin "1") (pinfunction "1_1") (pintype "passive"))
    )
    (net (code "26") (name "Net-(IC1B-+)") (class "Default")
      (node (ref "C2") (pin "+") (pinfunction "+_+") (pintype "passive"))
      (node (ref "D5") (pin "C") (pinfunction "C_C") (pintype "passive"))
      (node (ref "IC1") (pin "5") (pinfunction "+_5") (pintype "input"))
      (node (ref "TR1") (pin "P$1") (pinfunction "P$1_P$1") (pintype "bidirectional"))
    )
    (net (code "27") (name "Net-(IC1C-+)") (class "Default")
      (node (ref "C5") (pin "+") (pinfunction "+_+") (pintype "passive"))
      (node (ref "D6") (pin "C") (pinfunction "C_C") (pintype "passive"))
      (node (ref "IC1") (pin "10") (pinfunction "+_10") (pintype "input"))
      (node (ref "TR2") (pin "P$1") (pinfunction "P$1_P$1") (pintype "bidirectional"))
    )
    (net (code "28") (name "Net-(IC2A--IN)") (class "Default")
      (node (ref "IC2") (pin "2") (pinfunction "-IN_2") (pintype "input"))
      (node (ref "R49") (pin "2") (pinfunction "2_2") (pintype "passive"))
      (node (ref "R50") (pin "1") (pinfunction "1_1") (pintype "passive"))
    )
    (net (code "29") (name "Net-(IC2B--IN)") (class "Default")
      (node (ref "IC2") (pin "6") (pinfunction "-IN_6") (pintype "input"))
      (node (ref "IC2") (pin "7") (pinfunction "OUT_7") (pintype "output"))
    )
    (net (code "30") (name "Net-(IC3B-+)") (class "Default")
      (node (ref "C8") (pin "+") (pinfunction "+_+") (pintype "passive"))
      (node (ref "D7") (pin "C") (pinfunction "C_C") (pintype "passive"))
      (node (ref "IC3") (pin "5") (pinfunction "+_5") (pintype "input"))
      (node (ref "TR3") (pin "P$1") (pinfunction "P$1_P$1") (pintype "bidirectional"))
    )
    (net (code "31") (name "Net-(IC3C-+)") (class "Default")
      (node (ref "C11") (pin "+") (pinfunction "+_+") (pintype "passive"))
      (node (ref "D8") (pin "C") (pinfunction "C_C") (pintype "passive"))
      (node (ref "IC3") (pin "10") (pinfunction "+_10") (pintype "input"))
      (node (ref "TR4") (pin "P$1") (pinfunction "P$1_P$1") (pintype "bidirectional"))
    )
    (net (code "32") (name "Net-(IN1-TIP)") (class "Default")
      (node (ref "IN1") (pin "P$1_TIP") (pinfunction "TIP_P$1_TIP") (pintype "passive"))
      (node (ref "R10") (pin "1") (pinfunction "1_1") (pintype "passive"))
    )
    (net (code "33") (name "Net-(IN2-TIP)") (class "Default")
      (node (ref "IN2") (pin "P$1_TIP") (pinfunction "TIP_P$1_TIP") (pintype "passive"))
      (node (ref "R22") (pin "1") (pinfunction "1_1") (pintype "passive"))
    )
    (net (code "34") (name "Net-(IN3-TIP)") (class "Default")
      (node (ref "IN3") (pin "P$1_TIP") (pinfunction "TIP_P$1_TIP") (pintype "passive"))
      (node (ref "R34") (pin "1") (pinfunction "1_1") (pintype "passive"))
    )
    (net (code "35") (name "Net-(IN4-TIP)") (class "Default")
      (node (ref "IN4") (pin "P$1_TIP") (pinfunction "TIP_P$1_TIP") (pintype "passive"))
      (node (ref "R46") (pin "1") (pinfunction "1_1") (pintype "passive"))
    )
    (net (code "36") (name "Net-(L1-Pad1)") (class "Default")
      (node (ref "L1") (pin "1") (pinfunction "1_1") (pintype "passive"))
      (node (ref "U$1") (pin "10") (pinfunction "+12V_10") (pintype "bidirectional"))
      (node (ref "U$1") (pin "9") (pinfunction "+12V_9") (pintype "bidirectional"))
    )
    (net (code "37") (name "Net-(L2-Pad1)") (class "Default")
      (node (ref "L2") (pin "1") (pinfunction "1_1") (pintype "passive"))
      (node (ref "U$1") (pin "1") (pinfunction "-12V_1") (pintype "bidirectional"))
      (node (ref "U$1") (pin "2") (pinfunction "-12V_2") (pintype "bidirectional"))
    )
    (net (code "38") (name "Net-(OUT1-TIP)") (class "Default")
      (node (ref "OUT1") (pin "P$1_TIP") (pinfunction "TIP_P$1_TIP") (pintype "passive"))
      (node (ref "R11") (pin "2") (pinfunction "2_2") (pintype "passive"))
    )
    (net (code "39") (name "Net-(OUT2-TIP)") (class "Default")
      (node (ref "OUT2") (pin "P$1_TIP") (pinfunction "TIP_P$1_TIP") (pintype "passive"))
      (node (ref "R23") (pin "2") (pinfunction "2_2") (pintype "passive"))
    )
    (net (code "40") (name "Net-(OUT3-TIP)") (class "Default")
      (node (ref "OUT3") (pin "P$1_TIP") (pinfunction "TIP_P$1_TIP") (pintype "passive"))
      (node (ref "R35") (pin "2") (pinfunction "2_2") (pintype "passive"))
    )
    (net (code "41") (name "Net-(OUT4-TIP)") (class "Default")
      (node (ref "OUT4") (pin "P$1_TIP") (pinfunction "TIP_P$1_TIP") (pintype "passive"))
      (node (ref "R47") (pin "2") (pinfunction "2_2") (pintype "passive"))
    )
    (net (code "42") (name "Net-(R5-Pad2)") (class "Default")
      (node (ref "R5") (pin "2") (pinfunction "2_2") (pintype "passive"))
      (node (ref "R6") (pin "2") (pinfunction "2_2") (pintype "passive"))
      (node (ref "R7") (pin "2") (pinfunction "2_2") (pintype "passive"))
    )
    (net (code "43") (name "Net-(R9-Pad2)") (class "Default")
      (node (ref "R9") (pin "2") (pinfunction "2_2") (pintype "passive"))
      (node (ref "TR1") (pin "P$2A") (pinfunction "P$2_P$2A") (pintype "bidirectional"))
      (node (ref "TR1") (pin "P$2B") (pinfunction "P$2_P$2B") (pintype "bidirectional"))
      (node (ref "TR1") (pin "P$3") (pinfunction "P$3_P$3") (pintype "bidirectional"))
    )
    (net (code "44") (name "Net-(R17-Pad2)") (class "Default")
      (node (ref "R17") (pin "2") (pinfunction "2_2") (pintype "passive"))
      (node (ref "R18") (pin "2") (pinfunction "2_2") (pintype "passive"))
      (node (ref "R19") (pin "2") (pinfunction "2_2") (pintype "passive"))
    )
    (net (code "45") (name "Net-(R21-Pad2)") (class "Default")
      (node (ref "R21") (pin "2") (pinfunction "2_2") (pintype "passive"))
      (node (ref "TR2") (pin "P$2A") (pinfunction "P$2_P$2A") (pintype "bidirectional"))
      (node (ref "TR2") (pin "P$2B") (pinfunction "P$2_P$2B") (pintype "bidirectional"))
      (node (ref "TR2") (pin "P$3") (pinfunction "P$3_P$3") (pintype "bidirectional"))
    )
    (net (code "46") (name "Net-(R29-Pad2)") (class "Default")
      (node (ref "R29") (pin "2") (pinfunction "2_2") (pintype "passive"))
      (node (ref "R30") (pin "2") (pinfunction "2_2") (pintype "passive"))
      (node (ref "R31") (pin "2") (pinfunction "2_2") (pintype "passive"))
    )
    (net (code "47") (name "Net-(R33-Pad2)") (class "Default")
      (node (ref "R33") (pin "2") (pinfunction "2_2") (pintype "passive"))
      (node (ref "TR3") (pin "P$2A") (pinfunction "P$2_P$2A") (pintype "bidirectional"))
      (node (ref "TR3") (pin "P$2B") (pinfunction "P$2_P$2B") (pintype "bidirectional"))
      (node (ref "TR3") (pin "P$3") (pinfunction "P$3_P$3") (pintype "bidirectional"))
    )
    (net (code "48") (name "Net-(R41-Pad2)") (class "Default")
      (node (ref "R41") (pin "2") (pinfunction "2_2") (pintype "passive"))
      (node (ref "R42") (pin "2") (pinfunction "2_2") (pintype "passive"))
      (node (ref "R43") (pin "2") (pinfunction "2_2") (pintype "passive"))
    )
    (net (code "49") (name "Net-(R45-Pad2)") (class "Default")
      (node (ref "R45") (pin "2") (pinfunction "2_2") (pintype "passive"))
      (node (ref "TR4") (pin "P$2A") (pinfunction "P$2_P$2A") (pintype "bidirectional"))
      (node (ref "TR4") (pin "P$2B") (pinfunction "P$2_P$2B") (pintype "bidirectional"))
      (node (ref "TR4") (pin "P$3") (pinfunction "P$3_P$3") (pintype "bidirectional"))
    )
    (net (code "50") (name "Net-(T1-B)") (class "Default")
      (node (ref "R3") (pin "2") (pinfunction "2_2") (pintype "passive"))
      (node (ref "R4") (pin "2") (pinfunction "2_2") (pintype "passive"))
      (node (ref "T1") (pin "1") (pinfunction "B_1") (pintype "passive"))
    )
    (net (code "51") (name "Net-(T1-C)") (class "Default")
      (node (ref "R5") (pin "1") (pinfunction "1_1") (pintype "passive"))
      (node (ref "T1") (pin "3") (pinfunction "C_3") (pintype "passive"))
      (node (ref "T2") (pin "1") (pinfunction "B_1") (pintype "passive"))
    )
    (net (code "52") (name "Net-(T3-E)") (class "Default")
      (node (ref "D5") (pin "A") (pinfunction "A_A") (pintype "passive"))
      (node (ref "R8") (pin "2") (pinfunction "2_2") (pintype "passive"))
      (node (ref "T3") (pin "2") (pinfunction "E_2") (pintype "passive"))
    )
    (net (code "53") (name "Net-(T4-B)") (class "Default")
      (node (ref "R15") (pin "2") (pinfunction "2_2") (pintype "passive"))
      (node (ref "R16") (pin "2") (pinfunction "2_2") (pintype "passive"))
      (node (ref "T4") (pin "1") (pinfunction "B_1") (pintype "passive"))
    )
    (net (code "54") (name "Net-(T4-C)") (class "Default")
      (node (ref "R17") (pin "1") (pinfunction "1_1") (pintype "passive"))
      (node (ref "T4") (pin "3") (pinfunction "C_3") (pintype "passive"))
      (node (ref "T5") (pin "1") (pinfunction "B_1") (pintype "passive"))
    )
    (net (code "55") (name "Net-(T6-E)") (class "Default")
      (node (ref "D6") (pin "A") (pinfunction "A_A") (pintype "passive"))
      (node (ref "R20") (pin "2") (pinfunction "2_2") (pintype "passive"))
      (node (ref "T6") (pin "2") (pinfunction "E_2") (pintype "passive"))
    )
    (net (code "56") (name "Net-(T7-B)") (class "Default")
      (node (ref "R27") (pin "2") (pinfunction "2_2") (pintype "passive"))
      (node (ref "R28") (pin "2") (pinfunction "2_2") (pintype "passive"))
      (node (ref "T7") (pin "1") (pinfunction "B_1") (pintype "passive"))
    )
    (net (code "57") (name "Net-(T7-C)") (class "Default")
      (node (ref "R29") (pin "1") (pinfunction "1_1") (pintype "passive"))
      (node (ref "T7") (pin "3") (pinfunction "C_3") (pintype "passive"))
      (node (ref "T8") (pin "1") (pinfunction "B_1") (pintype "passive"))
    )
    (net (code "58") (name "Net-(T9-E)") (class "Default")
      (node (ref "D7") (pin "A") (pinfunction "A_A") (pintype "passive"))
      (node (ref "R32") (pin "2") (pinfunction "2_2") (pintype "passive"))
      (node (ref "T9") (pin "2") (pinfunction "E_2") (pintype "passive"))
    )
    (net (code "59") (name "Net-(T10-B)") (class "Default")
      (node (ref "R39") (pin "2") (pinfunction "2_2") (pintype "passive"))
      (node (ref "R40") (pin "2") (pinfunction "2_2") (pintype "passive"))
      (node (ref "T10") (pin "1") (pinfunction "B_1") (pintype "passive"))
    )
    (net (code "60") (name "Net-(T10-C)") (class "Default")
      (node (ref "R41") (pin "1") (pinfunction "1_1") (pintype "passive"))
      (node (ref "T10") (pin "3") (pinfunction "C_3") (pintype "passive"))
      (node (ref "T11") (pin "1") (pinfunction "B_1") (pintype "passive"))
    )
    (net (code "61") (name "Net-(T12-E)") (class "Default")
      (node (ref "D8") (pin "A") (pinfunction "A_A") (pintype "passive"))
      (node (ref "R44") (pin "2") (pinfunction "2_2") (pintype "passive"))
      (node (ref "T12") (pin "2") (pinfunction "E_2") (pintype "passive"))
    )
    (net (code "62") (name "Net-(TRIG1-TIP)") (class "Default")
      (node (ref "R1") (pin "1") (pinfunction "1_1") (pintype "passive"))
      (node (ref "TRIG1") (pin "P$1_TIP") (pinfunction "TIP_P$1_TIP") (pintype "passive"))
    )
    (net (code "63") (name "Net-(TRIG2-TIP)") (class "Default")
      (node (ref "R12") (pin "1") (pinfunction "1_1") (pintype "passive"))
      (node (ref "TRIG2") (pin "P$1_TIP") (pinfunction "TIP_P$1_TIP") (pintype "passive"))
    )
    (net (code "64") (name "Net-(TRIG3-TIP)") (class "Default")
      (node (ref "R25") (pin "1") (pinfunction "1_1") (pintype "passive"))
      (node (ref "TRIG3") (pin "P$1_TIP") (pinfunction "TIP_P$1_TIP") (pintype "passive"))
    )
    (net (code "65") (name "Net-(TRIG4-TIP)") (class "Default")
      (node (ref "R37") (pin "1") (pinfunction "1_1") (pintype "passive"))
      (node (ref "TRIG4") (pin "P$1_TIP") (pinfunction "TIP_P$1_TIP") (pintype "passive"))
    )
    (net (code "66") (name "OUT1") (class "Default")
      (node (ref "C3") (pin "2") (pinfunction "2_2") (pintype "passive"))
      (node (ref "IC1") (pin "1") (pinfunction "OUT_1") (pintype "output"))
      (node (ref "JP1") (pin "3") (pinfunction "3_3") (pintype "passive"))
      (node (ref "JP2") (pin "3") (pinfunction "3_3") (pintype "passive"))
      (node (ref "R11") (pin "1") (pinfunction "1_1") (pintype "passive"))
      (node (ref "R13") (pin "2") (pinfunction "2_2") (pintype "passive"))
    )
    (net (code "67") (name "OUT2") (class "Default")
      (node (ref "C6") (pin "2") (pinfunction "2_2") (pintype "passive"))
      (node (ref "IC1") (pin "14") (pinfunction "OUT_14") (pintype "output"))
      (node (ref "JP3") (pin "3") (pinfunction "3_3") (pintype "passive"))
      (node (ref "JP4") (pin "3") (pinfunction "3_3") (pintype "passive"))
      (node (ref "R23") (pin "1") (pinfunction "1_1") (pintype "passive"))
      (node (ref "R24") (pin "2") (pinfunction "2_2") (pintype "passive"))
    )
    (net (code "68") (name "OUT3") (class "Default")
      (node (ref "C9") (pin "2") (pinfunction "2_2") (pintype "passive"))
      (node (ref "IC3") (pin "1") (pinfunction "OUT_1") (pintype "output"))
      (node (ref "JP5") (pin "3") (pinfunction "3_3") (pintype "passive"))
      (node (ref "JP6") (pin "3") (pinfunction "3_3") (pintype "passive"))
      (node (ref "R35") (pin "1") (pinfunction "1_1") (pintype "passive"))
      (node (ref "R36") (pin "2") (pinfunction "2_2") (pintype "passive"))
    )
    (net (code "69") (name "OUT4") (class "Default")
      (node (ref "C12") (pin "2") (pinfunction "2_2") (pintype "passive"))
      (node (ref "IC3") (pin "14") (pinfunction "OUT_14") (pintype "output"))
      (node (ref "JP7") (pin "3") (pinfunction "3_3") (pintype "passive"))
      (node (ref "JP8") (pin "3") (pinfunction "3_3") (pintype "passive"))
      (node (ref "R47") (pin "1") (pinfunction "1_1") (pintype "passive"))
      (node (ref "R48") (pin "2") (pinfunction "2_2") (pintype "passive"))
    )
    (net (code "70") (name "TRIG1") (class "Default")
      (node (ref "JP1") (pin "1") (pinfunction "1_1") (pintype "passive"))
      (node (ref "JP2") (pin "1") (pinfunction "1_1") (pintype "passive"))
      (node (ref "R6") (pin "1") (pinfunction "1_1") (pintype "passive"))
      (node (ref "T2") (pin "3") (pinfunction "C_3") (pintype "passive"))
      (node (ref "T3") (pin "1") (pinfunction "B_1") (pintype "passive"))
    )
    (net (code "71") (name "TRIG2") (class "Default")
      (node (ref "JP3") (pin "1") (pinfunction "1_1") (pintype "passive"))
      (node (ref "JP4") (pin "1") (pinfunction "1_1") (pintype "passive"))
      (node (ref "R18") (pin "1") (pinfunction "1_1") (pintype "passive"))
      (node (ref "T5") (pin "3") (pinfunction "C_3") (pintype "passive"))
      (node (ref "T6") (pin "1") (pinfunction "B_1") (pintype "passive"))
    )
    (net (code "72") (name "TRIG3") (class "Default")
      (node (ref "JP5") (pin "1") (pinfunction "1_1") (pintype "passive"))
      (node (ref "JP6") (pin "1") (pinfunction "1_1") (pintype "passive"))
      (node (ref "R30") (pin "1") (pinfunction "1_1") (pintype "passive"))
      (node (ref "T8") (pin "3") (pinfunction "C_3") (pintype "passive"))
      (node (ref "T9") (pin "1") (pinfunction "B_1") (pintype "passive"))
    )
    (net (code "73") (name "TRIG4") (class "Default")
      (node (ref "JP7") (pin "1") (pinfunction "1_1") (pintype "passive"))
      (node (ref "JP8") (pin "1") (pinfunction "1_1") (pintype "passive"))
      (node (ref "R42") (pin "1") (pinfunction "1_1") (pintype "passive"))
      (node (ref "T11") (pin "3") (pinfunction "C_3") (pintype "passive"))
      (node (ref "T12") (pin "1") (pinfunction "B_1") (pintype "passive"))
    )
    (net (code "74") (name "V+") (class "Default")
      (node (ref "IC2") (pin "1") (pinfunction "OUT_1") (pintype "output"))
      (node (ref "JP10") (pin "2") (pinfunction "2_2") (pintype "passive"))
      (node (ref "JP11") (pin "3") (pinfunction "3_3") (pintype "passive"))
      (node (ref "JP12") (pin "3") (pinfunction "3_3") (pintype "passive"))
      (node (ref "JP9") (pin "2") (pinfunction "2_2") (pintype "passive"))
      (node (ref "R50") (pin "2") (pinfunction "2_2") (pintype "passive"))
      (node (ref "T12") (pin "3") (pinfunction "C_3") (pintype "passive"))
      (node (ref "T3") (pin "3") (pinfunction "C_3") (pintype "passive"))
      (node (ref "T6") (pin "3") (pinfunction "C_3") (pintype "passive"))
      (node (ref "T9") (pin "3") (pinfunction "C_3") (pintype "passive"))
    )
    (net (code "75") (name "unconnected-(IN1-SWITCH-PadP$2_SWITCH)") (class "Default")
      (node (ref "IN1") (pin "P$2_SWITCH") (pinfunction "SWITCH_P$2_SWITCH") (pintype "passive"))
    )
    (net (code "76") (name "unconnected-(IN2-SWITCH-PadP$2_SWITCH)") (class "Default")
      (node (ref "IN2") (pin "P$2_SWITCH") (pinfunction "SWITCH_P$2_SWITCH") (pintype "passive"))
    )
    (net (code "77") (name "unconnected-(IN3-SWITCH-PadP$2_SWITCH)") (class "Default")
      (node (ref "IN3") (pin "P$2_SWITCH") (pinfunction "SWITCH_P$2_SWITCH") (pintype "passive"))
    )
    (net (code "78") (name "unconnected-(IN4-SWITCH-PadP$2_SWITCH)") (class "Default")
      (node (ref "IN4") (pin "P$2_SWITCH") (pinfunction "SWITCH_P$2_SWITCH") (pintype "passive"))
    )
    (net (code "79") (name "unconnected-(OUT1-SWITCH-PadP$2_SWITCH)") (class "Default")
      (node (ref "OUT1") (pin "P$2_SWITCH") (pinfunction "SWITCH_P$2_SWITCH") (pintype "passive"))
    )
    (net (code "80") (name "unconnected-(OUT2-SWITCH-PadP$2_SWITCH)") (class "Default")
      (node (ref "OUT2") (pin "P$2_SWITCH") (pinfunction "SWITCH_P$2_SWITCH") (pintype "passive"))
    )
    (net (code "81") (name "unconnected-(OUT3-SWITCH-PadP$2_SWITCH)") (class "Default")
      (node (ref "OUT3") (pin "P$2_SWITCH") (pinfunction "SWITCH_P$2_SWITCH") (pintype "passive"))
    )
    (net (code "82") (name "unconnected-(OUT4-SWITCH-PadP$2_SWITCH)") (class "Default")
      (node (ref "OUT4") (pin "P$2_SWITCH") (pinfunction "SWITCH_P$2_SWITCH") (pintype "passive"))
    )
    (net (code "83") (name "unconnected-(TRIG1-SWITCH-PadP$2_SWITCH)") (class "Default")
      (node (ref "TRIG1") (pin "P$2_SWITCH") (pinfunction "SWITCH_P$2_SWITCH") (pintype "passive"))
    )
    (net (code "84") (name "unconnected-(TRIG2-SWITCH-PadP$2_SWITCH)") (class "Default")
      (node (ref "TRIG2") (pin "P$2_SWITCH") (pinfunction "SWITCH_P$2_SWITCH") (pintype "passive"))
    )
    (net (code "85") (name "unconnected-(TRIG3-SWITCH-PadP$2_SWITCH)") (class "Default")
      (node (ref "TRIG3") (pin "P$2_SWITCH") (pinfunction "SWITCH_P$2_SWITCH") (pintype "passive"))
    )
    (net (code "86") (name "unconnected-(TRIG4-SWITCH-PadP$2_SWITCH)") (class "Default")
      (node (ref "TRIG4") (pin "P$2_SWITCH") (pinfunction "SWITCH_P$2_SWITCH") (pintype "passive"))
    )
  )
)
